# HyperArmBoardREV2.net
KiCad netlist of a schematic drawn in EAGLE
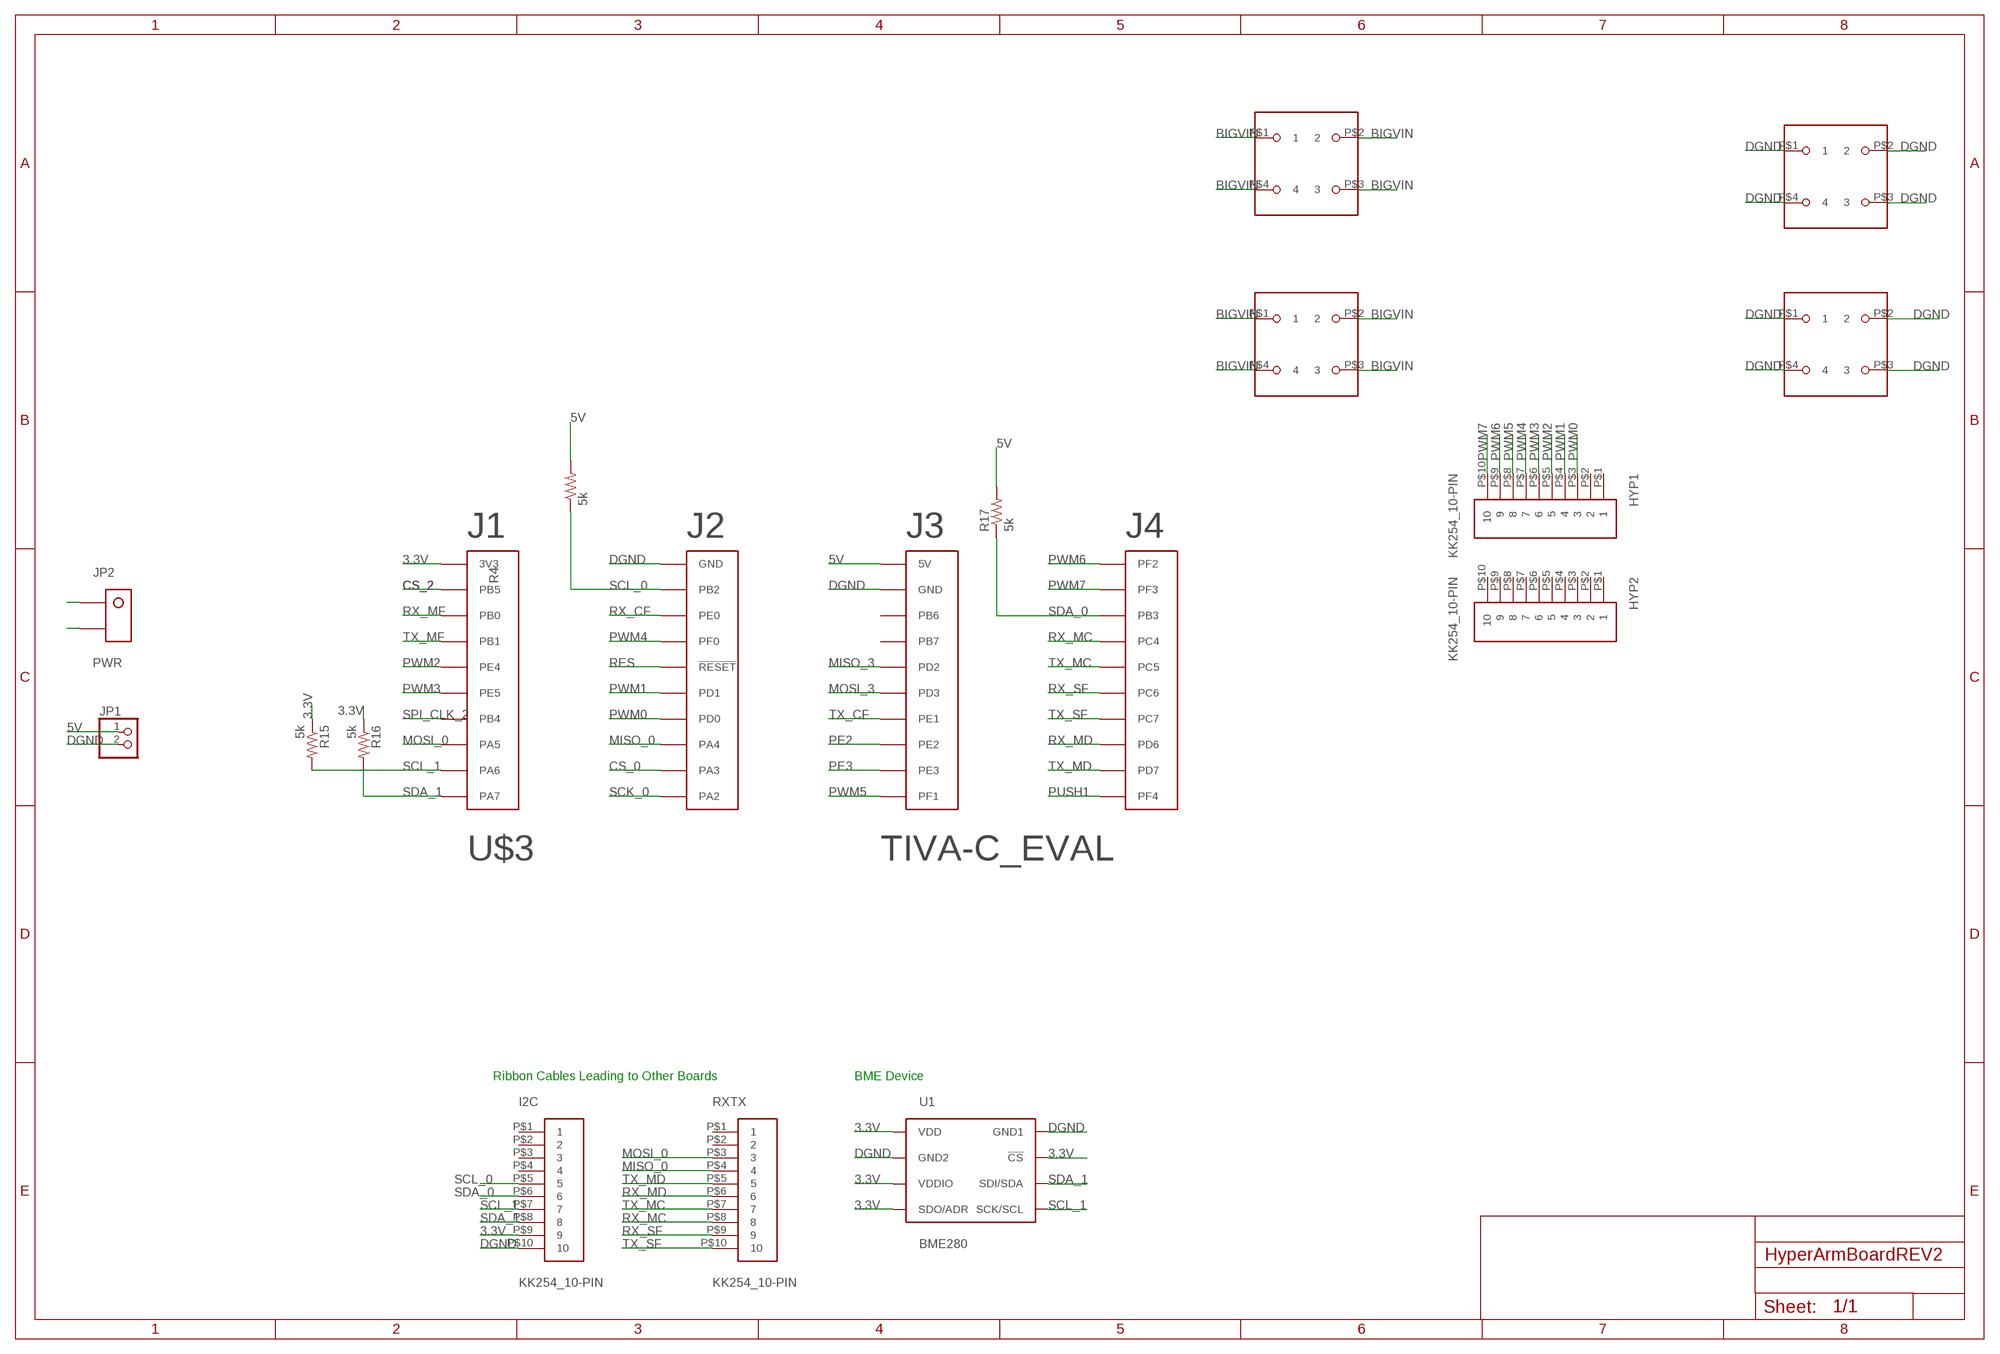
[diagram p0: schematic, sheet 1]

(export (version "E")
  (design (tool "Eeschema 10.0.6"))
  (components
    (comp (ref "HYP1")
      (value "KK254_10-PIN")
      (footprint "eagle-import:KK254_10-PIN")
      (libsource (lib "eagle-import") (part "KK254_10-PIN"))
    )
    (comp (ref "HYP2")
      (value "KK254_10-PIN")
      (footprint "eagle-import:KK254_10-PIN")
      (libsource (lib "eagle-import") (part "KK254_10-PIN"))
    )
    (comp (ref "I2C")
      (value "KK254_10-PIN")
      (footprint "eagle-import:KK254_10-PIN")
      (libsource (lib "eagle-import") (part "KK254_10-PIN"))
    )
    (comp (ref "JP1")
      (value "PINHD-1X2")
      (footprint "eagle-import:1X02")
      (libsource (lib "eagle-import") (part "PINHD-1X2"))
    )
    (comp (ref "JP2")
      (value "PWR")
      (footprint "eagle-import:SUPERSABRE_2CIRCUIT")
      (libsource (lib "eagle-import") (part "2_SUPERSABRE"))
    )
    (comp (ref "R4")
      (value "5k")
      (footprint "eagle-import:R0805")
      (libsource (lib "eagle-import") (part "R-US_R0805"))
    )
    (comp (ref "R15")
      (value "5k")
      (footprint "eagle-import:R0805")
      (libsource (lib "eagle-import") (part "R-US_R0805"))
    )
    (comp (ref "R16")
      (value "5k")
      (footprint "eagle-import:R0805")
      (libsource (lib "eagle-import") (part "R-US_R0805"))
    )
    (comp (ref "R17")
      (value "5k")
      (footprint "eagle-import:R0805")
      (libsource (lib "eagle-import") (part "R-US_R0805"))
    )
    (comp (ref "RXTX")
      (value "KK254_10-PIN")
      (footprint "eagle-import:KK254_10-PIN")
      (libsource (lib "eagle-import") (part "KK254_10-PIN"))
    )
    (comp (ref "U$3")
      (value "TIVA-C_EVAL")
      (footprint "eagle-import:TIVA-C_EVAL")
      (libsource (lib "eagle-import") (part "TIVA-C_EVAL"))
    )
    (comp (ref "U$4")
      (value "BCS-106-L-D-PE-BE")
      (footprint "eagle-import:4-PIN-BIGPOWER")
      (libsource (lib "eagle-import") (part "BCS-106-L-D-PE-BE"))
    )
    (comp (ref "U$5")
      (value "BCS-106-L-D-PE-BE")
      (footprint "eagle-import:4-PIN-BIGPOWER")
      (libsource (lib "eagle-import") (part "BCS-106-L-D-PE-BE"))
    )
    (comp (ref "U$6")
      (value "BCS-106-L-D-PE-BE")
      (footprint "eagle-import:4-PIN-BIGPOWER")
      (libsource (lib "eagle-import") (part "BCS-106-L-D-PE-BE"))
    )
    (comp (ref "U$7")
      (value "BCS-106-L-D-PE-BE")
      (footprint "eagle-import:4-PIN-BIGPOWER")
      (libsource (lib "eagle-import") (part "BCS-106-L-D-PE-BE"))
    )
    (comp (ref "U1")
      (value "BME280")
      (footprint "eagle-import:BME280_LGA")
      (libsource (lib "eagle-import") (part "BME280"))
    )
  )
  (nets
    (net (code "1") (name "/3.3V") (class "Default")
      (node (ref "I2C") (pin "P$9") (pinfunction "9_P$9") (pintype "bidirectional"))
      (node (ref "R15") (pin "1") (pinfunction "1_1") (pintype "passive"))
      (node (ref "R16") (pin "1") (pinfunction "1_1") (pintype "passive"))
      (node (ref "U$3") (pin "1-1") (pinfunction "3V3_1-1") (pintype "bidirectional"))
      (node (ref "U1") (pin "P$2") (pinfunction "~{CS}_P$2") (pintype "bidirectional"))
      (node (ref "U1") (pin "P$5") (pinfunction "SDO/ADR_P$5") (pintype "bidirectional"))
      (node (ref "U1") (pin "P$6") (pinfunction "VDDIO_P$6") (pintype "bidirectional"))
      (node (ref "U1") (pin "P$8") (pinfunction "VDD_P$8") (pintype "bidirectional"))
    )
    (net (code "2") (name "/5V") (class "Default")
      (node (ref "JP1") (pin "1") (pinfunction "1_1") (pintype "passive"))
      (node (ref "R17") (pin "2") (pinfunction "2_2") (pintype "passive"))
      (node (ref "R4") (pin "2") (pinfunction "2_2") (pintype "passive"))
      (node (ref "U$3") (pin "3-1") (pinfunction "5V_3-1") (pintype "bidirectional"))
    )
    (net (code "3") (name "/BIGVIN") (class "Default")
      (node (ref "JP2") (pin "P$1") (pinfunction "P$1_P$1") (pintype "bidirectional"))
      (node (ref "U$4") (pin "P$1") (pinfunction "1_P$1") (pintype "bidirectional"))
      (node (ref "U$4") (pin "P$2") (pinfunction "2_P$2") (pintype "bidirectional"))
      (node (ref "U$4") (pin "P$3") (pinfunction "3_P$3") (pintype "bidirectional"))
      (node (ref "U$4") (pin "P$4") (pinfunction "4_P$4") (pintype "bidirectional"))
      (node (ref "U$5") (pin "P$1") (pinfunction "1_P$1") (pintype "bidirectional"))
      (node (ref "U$5") (pin "P$2") (pinfunction "2_P$2") (pintype "bidirectional"))
      (node (ref "U$5") (pin "P$3") (pinfunction "3_P$3") (pintype "bidirectional"))
      (node (ref "U$5") (pin "P$4") (pinfunction "4_P$4") (pintype "bidirectional"))
    )
    (net (code "4") (name "/CS_0") (class "Default")
      (node (ref "U$3") (pin "2-9") (pinfunction "PA3_2-9") (pintype "bidirectional"))
    )
    (net (code "5") (name "/CS_2") (class "Default")
      (node (ref "U$3") (pin "1-2") (pinfunction "PB5_1-2") (pintype "bidirectional"))
    )
    (net (code "6") (name "/DGND") (class "Default")
      (node (ref "I2C") (pin "P$10") (pinfunction "10_P$10") (pintype "bidirectional"))
      (node (ref "JP1") (pin "2") (pinfunction "2_2") (pintype "passive"))
      (node (ref "JP2") (pin "P$2") (pinfunction "P$2_P$2") (pintype "bidirectional"))
      (node (ref "U$3") (pin "2-1") (pinfunction "GND_2-1") (pintype "bidirectional"))
      (node (ref "U$3") (pin "3-2") (pinfunction "GND_3-2") (pintype "bidirectional"))
      (node (ref "U$6") (pin "P$1") (pinfunction "1_P$1") (pintype "bidirectional"))
      (node (ref "U$6") (pin "P$2") (pinfunction "2_P$2") (pintype "bidirectional"))
      (node (ref "U$6") (pin "P$3") (pinfunction "3_P$3") (pintype "bidirectional"))
      (node (ref "U$6") (pin "P$4") (pinfunction "4_P$4") (pintype "bidirectional"))
      (node (ref "U$7") (pin "P$1") (pinfunction "1_P$1") (pintype "bidirectional"))
      (node (ref "U$7") (pin "P$2") (pinfunction "2_P$2") (pintype "bidirectional"))
      (node (ref "U$7") (pin "P$3") (pinfunction "3_P$3") (pintype "bidirectional"))
      (node (ref "U$7") (pin "P$4") (pinfunction "4_P$4") (pintype "bidirectional"))
      (node (ref "U1") (pin "P$1") (pinfunction "GND1_P$1") (pintype "bidirectional"))
      (node (ref "U1") (pin "P$7") (pinfunction "GND2_P$7") (pintype "bidirectional"))
    )
    (net (code "7") (name "/MISO_0") (class "Default")
      (node (ref "RXTX") (pin "P$4") (pinfunction "4_P$4") (pintype "bidirectional"))
      (node (ref "U$3") (pin "2-8") (pinfunction "PA4_2-8") (pintype "bidirectional"))
    )
    (net (code "8") (name "/MISO_3") (class "Default")
      (node (ref "U$3") (pin "3-5") (pinfunction "PD2_3-5") (pintype "bidirectional"))
    )
    (net (code "9") (name "/MOSI_0") (class "Default")
      (node (ref "RXTX") (pin "P$3") (pinfunction "3_P$3") (pintype "bidirectional"))
      (node (ref "U$3") (pin "1-8") (pinfunction "PA5_1-8") (pintype "bidirectional"))
    )
    (net (code "10") (name "/MOSI_3") (class "Default")
      (node (ref "U$3") (pin "3-6") (pinfunction "PD3_3-6") (pintype "bidirectional"))
    )
    (net (code "11") (name "/PE2") (class "Default")
      (node (ref "U$3") (pin "3-8") (pinfunction "PE2_3-8") (pintype "bidirectional"))
    )
    (net (code "12") (name "/PE3") (class "Default")
      (node (ref "U$3") (pin "3-9") (pinfunction "PE3_3-9") (pintype "bidirectional"))
    )
    (net (code "13") (name "/PUSH1") (class "Default")
      (node (ref "U$3") (pin "4-10") (pinfunction "PF4_4-10") (pintype "bidirectional"))
    )
    (net (code "14") (name "/PWM0") (class "Default")
      (node (ref "HYP1") (pin "P$3") (pinfunction "3_P$3") (pintype "bidirectional"))
      (node (ref "U$3") (pin "2-7") (pinfunction "PD0_2-7") (pintype "bidirectional"))
    )
    (net (code "15") (name "/PWM1") (class "Default")
      (node (ref "HYP1") (pin "P$4") (pinfunction "4_P$4") (pintype "bidirectional"))
      (node (ref "U$3") (pin "2-6") (pinfunction "PD1_2-6") (pintype "bidirectional"))
    )
    (net (code "16") (name "/PWM2") (class "Default")
      (node (ref "HYP1") (pin "P$5") (pinfunction "5_P$5") (pintype "bidirectional"))
      (node (ref "U$3") (pin "1-5") (pinfunction "PE4_1-5") (pintype "bidirectional"))
    )
    (net (code "17") (name "/PWM3") (class "Default")
      (node (ref "HYP1") (pin "P$6") (pinfunction "6_P$6") (pintype "bidirectional"))
      (node (ref "U$3") (pin "1-6") (pinfunction "PE5_1-6") (pintype "bidirectional"))
    )
    (net (code "18") (name "/PWM4") (class "Default")
      (node (ref "HYP1") (pin "P$7") (pinfunction "7_P$7") (pintype "bidirectional"))
      (node (ref "U$3") (pin "2-4") (pinfunction "PF0_2-4") (pintype "bidirectional"))
    )
    (net (code "19") (name "/PWM5") (class "Default")
      (node (ref "HYP1") (pin "P$8") (pinfunction "8_P$8") (pintype "bidirectional"))
      (node (ref "U$3") (pin "3-10") (pinfunction "PF1_3-10") (pintype "bidirectional"))
    )
    (net (code "20") (name "/PWM6") (class "Default")
      (node (ref "HYP1") (pin "P$9") (pinfunction "9_P$9") (pintype "bidirectional"))
      (node (ref "U$3") (pin "4-1") (pinfunction "PF2_4-1") (pintype "bidirectional"))
    )
    (net (code "21") (name "/PWM7") (class "Default")
      (node (ref "HYP1") (pin "P$10") (pinfunction "10_P$10") (pintype "bidirectional"))
      (node (ref "U$3") (pin "4-2") (pinfunction "PF3_4-2") (pintype "bidirectional"))
    )
    (net (code "22") (name "/RES") (class "Default")
      (node (ref "U$3") (pin "2-5") (pinfunction "~{RESET}_2-5") (pintype "bidirectional"))
    )
    (net (code "23") (name "/RX_CF") (class "Default")
      (node (ref "U$3") (pin "2-3") (pinfunction "PE0_2-3") (pintype "bidirectional"))
    )
    (net (code "24") (name "/RX_MC") (class "Default")
      (node (ref "RXTX") (pin "P$8") (pinfunction "8_P$8") (pintype "bidirectional"))
      (node (ref "U$3") (pin "4-4") (pinfunction "PC4_4-4") (pintype "bidirectional"))
    )
    (net (code "25") (name "/RX_MD") (class "Default")
      (node (ref "RXTX") (pin "P$6") (pinfunction "6_P$6") (pintype "bidirectional"))
      (node (ref "U$3") (pin "4-8") (pinfunction "PD6_4-8") (pintype "bidirectional"))
    )
    (net (code "26") (name "/RX_MF") (class "Default")
      (node (ref "U$3") (pin "1-3") (pinfunction "PB0_1-3") (pintype "bidirectional"))
    )
    (net (code "27") (name "/RX_SF") (class "Default")
      (node (ref "RXTX") (pin "P$9") (pinfunction "9_P$9") (pintype "bidirectional"))
      (node (ref "U$3") (pin "4-6") (pinfunction "PC6_4-6") (pintype "bidirectional"))
    )
    (net (code "28") (name "/SCK_0") (class "Default")
      (node (ref "U$3") (pin "2-10") (pinfunction "PA2_2-10") (pintype "bidirectional"))
    )
    (net (code "29") (name "/SCL_0") (class "Default")
      (node (ref "I2C") (pin "P$5") (pinfunction "5_P$5") (pintype "bidirectional"))
      (node (ref "R4") (pin "1") (pinfunction "1_1") (pintype "passive"))
      (node (ref "U$3") (pin "2-2") (pinfunction "PB2_2-2") (pintype "bidirectional"))
    )
    (net (code "30") (name "/SCL_1") (class "Default")
      (node (ref "I2C") (pin "P$7") (pinfunction "7_P$7") (pintype "bidirectional"))
      (node (ref "R15") (pin "2") (pinfunction "2_2") (pintype "passive"))
      (node (ref "U$3") (pin "1-9") (pinfunction "PA6_1-9") (pintype "bidirectional"))
      (node (ref "U1") (pin "P$4") (pinfunction "SCK/SCL_P$4") (pintype "bidirectional"))
    )
    (net (code "31") (name "/SDA_0") (class "Default")
      (node (ref "I2C") (pin "P$6") (pinfunction "6_P$6") (pintype "bidirectional"))
      (node (ref "R17") (pin "1") (pinfunction "1_1") (pintype "passive"))
      (node (ref "U$3") (pin "4-3") (pinfunction "PB3_4-3") (pintype "bidirectional"))
    )
    (net (code "32") (name "/SDA_1") (class "Default")
      (node (ref "I2C") (pin "P$8") (pinfunction "8_P$8") (pintype "bidirectional"))
      (node (ref "R16") (pin "2") (pinfunction "2_2") (pintype "passive"))
      (node (ref "U$3") (pin "1-10") (pinfunction "PA7_1-10") (pintype "bidirectional"))
      (node (ref "U1") (pin "P$3") (pinfunction "SDI/SDA_P$3") (pintype "bidirectional"))
    )
    (net (code "33") (name "/SPI_CLK_2") (class "Default")
      (node (ref "U$3") (pin "1-7") (pinfunction "PB4_1-7") (pintype "bidirectional"))
    )
    (net (code "34") (name "/TX_CF") (class "Default")
      (node (ref "U$3") (pin "3-7") (pinfunction "PE1_3-7") (pintype "bidirectional"))
    )
    (net (code "35") (name "/TX_MC") (class "Default")
      (node (ref "RXTX") (pin "P$7") (pinfunction "7_P$7") (pintype "bidirectional"))
      (node (ref "U$3") (pin "4-5") (pinfunction "PC5_4-5") (pintype "bidirectional"))
    )
    (net (code "36") (name "/TX_MD") (class "Default")
      (node (ref "RXTX") (pin "P$5") (pinfunction "5_P$5") (pintype "bidirectional"))
      (node (ref "U$3") (pin "4-9") (pinfunction "PD7_4-9") (pintype "bidirectional"))
    )
    (net (code "37") (name "/TX_MF") (class "Default")
      (node (ref "U$3") (pin "1-4") (pinfunction "PB1_1-4") (pintype "bidirectional"))
    )
    (net (code "38") (name "/TX_SF") (class "Default")
      (node (ref "RXTX") (pin "P$10") (pinfunction "10_P$10") (pintype "bidirectional"))
      (node (ref "U$3") (pin "4-7") (pinfunction "PC7_4-7") (pintype "bidirectional"))
    )
    (net (code "39") (name "unconnected-(HYP1-1-PadP$1)") (class "Default")
      (node (ref "HYP1") (pin "P$1") (pinfunction "1_P$1") (pintype "bidirectional"))
    )
    (net (code "40") (name "unconnected-(HYP1-2-PadP$2)") (class "Default")
      (node (ref "HYP1") (pin "P$2") (pinfunction "2_P$2") (pintype "bidirectional"))
    )
    (net (code "41") (name "unconnected-(HYP2-1-PadP$1)") (class "Default")
      (node (ref "HYP2") (pin "P$1") (pinfunction "1_P$1") (pintype "bidirectional"))
    )
    (net (code "42") (name "unconnected-(HYP2-2-PadP$2)") (class "Default")
      (node (ref "HYP2") (pin "P$2") (pinfunction "2_P$2") (pintype "bidirectional"))
    )
    (net (code "43") (name "unconnected-(HYP2-3-PadP$3)") (class "Default")
      (node (ref "HYP2") (pin "P$3") (pinfunction "3_P$3") (pintype "bidirectional"))
    )
    (net (code "44") (name "unconnected-(HYP2-4-PadP$4)") (class "Default")
      (node (ref "HYP2") (pin "P$4") (pinfunction "4_P$4") (pintype "bidirectional"))
    )
    (net (code "45") (name "unconnected-(HYP2-5-PadP$5)") (class "Default")
      (node (ref "HYP2") (pin "P$5") (pinfunction "5_P$5") (pintype "bidirectional"))
    )
    (net (code "46") (name "unconnected-(HYP2-6-PadP$6)") (class "Default")
      (node (ref "HYP2") (pin "P$6") (pinfunction "6_P$6") (pintype "bidirectional"))
    )
    (net (code "47") (name "unconnected-(HYP2-7-PadP$7)") (class "Default")
      (node (ref "HYP2") (pin "P$7") (pinfunction "7_P$7") (pintype "bidirectional"))
    )
    (net (code "48") (name "unconnected-(HYP2-8-PadP$8)") (class "Default")
      (node (ref "HYP2") (pin "P$8") (pinfunction "8_P$8") (pintype "bidirectional"))
    )
    (net (code "49") (name "unconnected-(HYP2-9-PadP$9)") (class "Default")
      (node (ref "HYP2") (pin "P$9") (pinfunction "9_P$9") (pintype "bidirectional"))
    )
    (net (code "50") (name "unconnected-(HYP2-10-PadP$10)") (class "Default")
      (node (ref "HYP2") (pin "P$10") (pinfunction "10_P$10") (pintype "bidirectional"))
    )
    (net (code "51") (name "unconnected-(I2C-1-PadP$1)") (class "Default")
      (node (ref "I2C") (pin "P$1") (pinfunction "1_P$1") (pintype "bidirectional"))
    )
    (net (code "52") (name "unconnected-(I2C-2-PadP$2)") (class "Default")
      (node (ref "I2C") (pin "P$2") (pinfunction "2_P$2") (pintype "bidirectional"))
    )
    (net (code "53") (name "unconnected-(I2C-3-PadP$3)") (class "Default")
      (node (ref "I2C") (pin "P$3") (pinfunction "3_P$3") (pintype "bidirectional"))
    )
    (net (code "54") (name "unconnected-(I2C-4-PadP$4)") (class "Default")
      (node (ref "I2C") (pin "P$4") (pinfunction "4_P$4") (pintype "bidirectional"))
    )
    (net (code "55") (name "unconnected-(RXTX-1-PadP$1)") (class "Default")
      (node (ref "RXTX") (pin "P$1") (pinfunction "1_P$1") (pintype "bidirectional"))
    )
    (net (code "56") (name "unconnected-(RXTX-2-PadP$2)") (class "Default")
      (node (ref "RXTX") (pin "P$2") (pinfunction "2_P$2") (pintype "bidirectional"))
    )
    (net (code "57") (name "unconnected-(U$3-PB6-Pad3-3)") (class "Default")
      (node (ref "U$3") (pin "3-3") (pinfunction "PB6_3-3") (pintype "bidirectional"))
    )
    (net (code "58") (name "unconnected-(U$3-PB7-Pad3-4)") (class "Default")
      (node (ref "U$3") (pin "3-4") (pinfunction "PB7_3-4") (pintype "bidirectional"))
    )
  )
)
